# Peripherals.net
KiCad netlist of a schematic drawn in Altium Designer
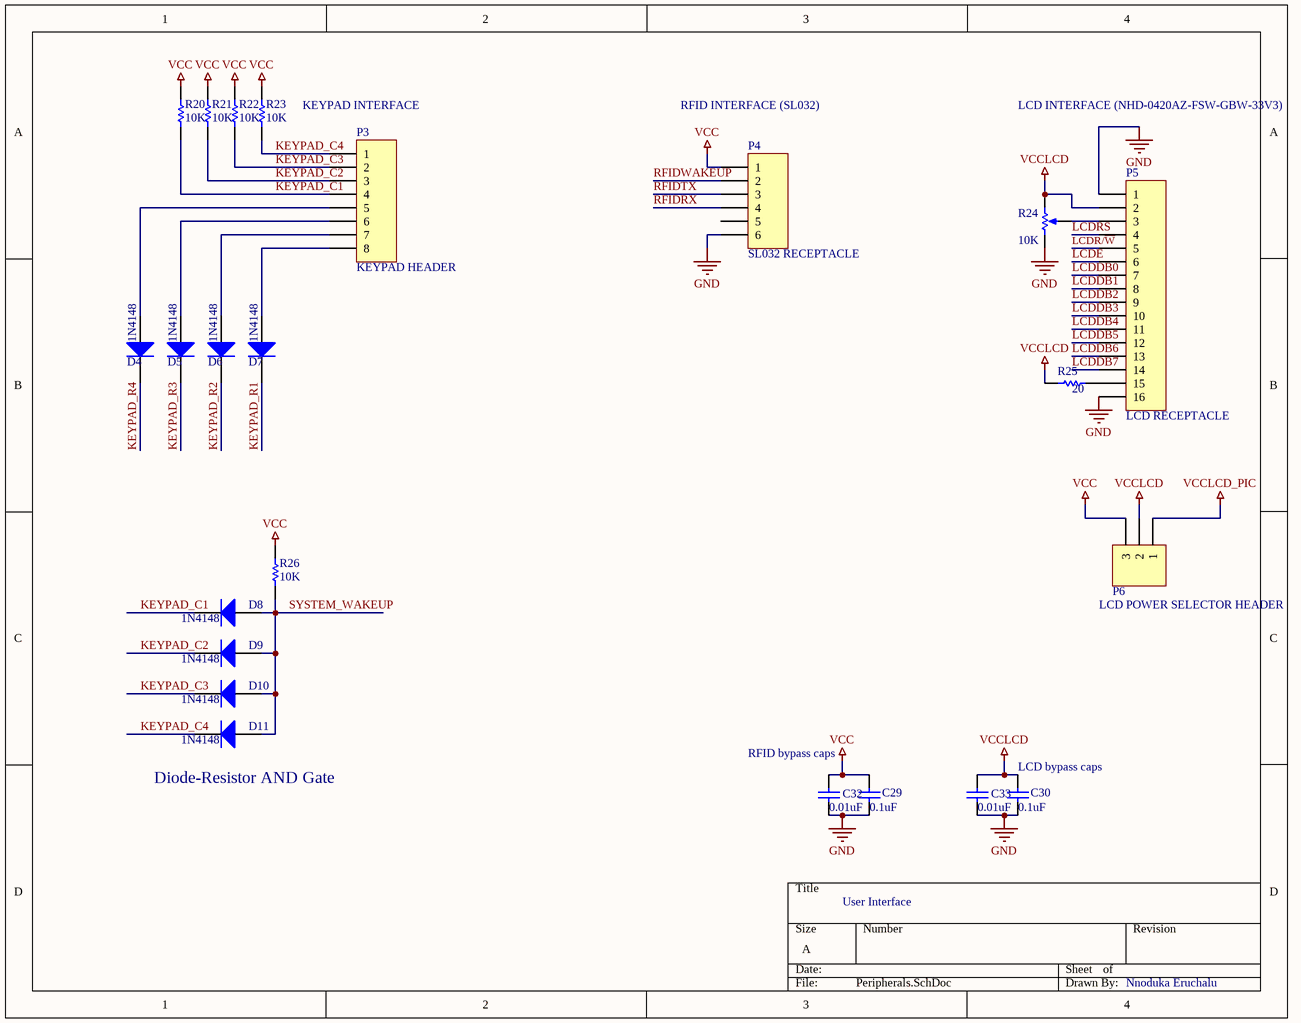
[diagram p0: Peripherals.SchDoc]

(export (version "E")
  (design (tool "Eeschema 10.0.6"))
  (components
    (comp (ref "C29")
      (value "0.1uF")
      (footprint "2012[0805]")
      (description "Ceramic Chip Capacitor - Standard")
      (fields (field (name "Comment") "C2012X7R1H104K/0.85") (field (name "PUBLISHER") "Altium Limited"))
      (libsource (lib "KEMET Chip Capacitor") (part "C0805"))
    )
    (comp (ref "C30")
      (value "0.1uF")
      (footprint "2012[0805]")
      (description "Ceramic Chip Capacitor - Standard")
      (fields (field (name "Comment") "C2012X7R1H104K/0.85") (field (name "PUBLISHER") "Altium Limited"))
      (libsource (lib "KEMET Chip Capacitor") (part "C0805"))
    )
    (comp (ref "C32")
      (value "0.01uF")
      (footprint "2012[0805]")
      (description "Ceramic Chip Capacitor - Standard")
      (fields (field (name "Comment") "C2012X7R2E103K") (field (name "PUBLISHER") "Altium Limited"))
      (libsource (lib "KEMET Chip Capacitor") (part "C0805"))
    )
    (comp (ref "C33")
      (value "0.01uF")
      (footprint "2012[0805]")
      (description "Ceramic Chip Capacitor - Standard")
      (fields (field (name "Comment") "C2012X7R2E103K") (field (name "PUBLISHER") "Altium Limited"))
      (libsource (lib "KEMET Chip Capacitor") (part "C0805"))
    )
    (comp (ref "D4")
      (value "1N4148")
      (footprint "easypay:SOD123")
      (description "High Conductance Fast Diode")
      (fields (field (name "PUBLISHER") "Altium Limited"))
      (libsource (lib "Miscellaneous Devices") (part "Diode 1N4148"))
    )
    (comp (ref "D5")
      (value "1N4148")
      (footprint "easypay:SOD123")
      (description "High Conductance Fast Diode")
      (fields (field (name "PUBLISHER") "Altium Limited"))
      (libsource (lib "Miscellaneous Devices") (part "Diode 1N4148"))
    )
    (comp (ref "D6")
      (value "1N4148")
      (footprint "easypay:SOD123")
      (description "High Conductance Fast Diode")
      (fields (field (name "PUBLISHER") "Altium Limited"))
      (libsource (lib "Miscellaneous Devices") (part "Diode 1N4148"))
    )
    (comp (ref "D7")
      (value "1N4148")
      (footprint "easypay:SOD123")
      (description "High Conductance Fast Diode")
      (fields (field (name "PUBLISHER") "Altium Limited"))
      (libsource (lib "Miscellaneous Devices") (part "Diode 1N4148"))
    )
    (comp (ref "D8")
      (value "1N4148")
      (footprint "easypay:SOD123")
      (description "High Conductance Fast Diode")
      (fields (field (name "PUBLISHER") "Altium Limited"))
      (libsource (lib "Miscellaneous Devices") (part "Diode 1N4148"))
    )
    (comp (ref "D9")
      (value "1N4148")
      (footprint "easypay:SOD123")
      (description "High Conductance Fast Diode")
      (fields (field (name "PUBLISHER") "Altium Limited"))
      (libsource (lib "Miscellaneous Devices") (part "Diode 1N4148"))
    )
    (comp (ref "D10")
      (value "1N4148")
      (footprint "easypay:SOD123")
      (description "High Conductance Fast Diode")
      (fields (field (name "PUBLISHER") "Altium Limited"))
      (libsource (lib "Miscellaneous Devices") (part "Diode 1N4148"))
    )
    (comp (ref "D11")
      (value "1N4148")
      (footprint "easypay:SOD123")
      (description "High Conductance Fast Diode")
      (fields (field (name "PUBLISHER") "Altium Limited"))
      (libsource (lib "Miscellaneous Devices") (part "Diode 1N4148"))
    )
    (comp (ref "P3")
      (value "KEYPAD HEADER")
      (footprint "HDR1X8")
      (description "Header, 8-Pin")
      (fields (field (name "PUBLISHER") "Altium Limited"))
      (libsource (lib "Miscellaneous Connectors") (part "Header 8"))
    )
    (comp (ref "P4")
      (value "SL032 RECEPTACLE")
      (footprint "HDR1X6")
      (description "Header, 6-Pin")
      (fields (field (name "PUBLISHER") "Altium Limited"))
      (libsource (lib "Miscellaneous Connectors") (part "Header 6"))
    )
    (comp (ref "P5")
      (value "LCD RECEPTACLE")
      (footprint "HDR1X16")
      (description "Header, 16-Pin")
      (fields (field (name "PUBLISHER") "Altium Limited"))
      (libsource (lib "Miscellaneous Connectors") (part "Header 16"))
    )
    (comp (ref "P6")
      (value "LCD POWER SELECTOR HEADER")
      (footprint "HDR1X3")
      (description "Header, 3-Pin")
      (fields (field (name "PUBLISHER") "Altium Limited"))
      (libsource (lib "Miscellaneous Connectors") (part "Header 3"))
    )
    (comp (ref "R20")
      (value "10K")
      (footprint "Miscellaneous Devices:2012[0805]")
      (description "Resistor")
      (fields (field (name "Comment") "ERJ-6GEYJ103V") (field (name "PUBLISHER") "Altium Limited"))
      (libsource (lib "Miscellaneous Devices") (part "Res1"))
    )
    (comp (ref "R21")
      (value "10K")
      (footprint "Miscellaneous Devices:2012[0805]")
      (description "Resistor")
      (fields (field (name "Comment") "ERJ-6GEYJ103V") (field (name "PUBLISHER") "Altium Limited"))
      (libsource (lib "Miscellaneous Devices") (part "Res1"))
    )
    (comp (ref "R22")
      (value "10K")
      (footprint "Miscellaneous Devices:2012[0805]")
      (description "Resistor")
      (fields (field (name "Comment") "ERJ-6GEYJ103V") (field (name "PUBLISHER") "Altium Limited"))
      (libsource (lib "Miscellaneous Devices") (part "Res1"))
    )
    (comp (ref "R23")
      (value "10K")
      (footprint "Miscellaneous Devices:2012[0805]")
      (description "Resistor")
      (fields (field (name "Comment") "ERJ-6GEYJ103V") (field (name "PUBLISHER") "Altium Limited"))
      (libsource (lib "Miscellaneous Devices") (part "Res1"))
    )
    (comp (ref "R24")
      (value "10K")
      (footprint "TC33")
      (description "Potentiometer")
      (fields (field (name "Comment") "TC33X-2-103E") (field (name "PUBLISHER") "Altium Limited"))
      (libsource (lib "Miscellaneous Devices") (part "RPot"))
    )
    (comp (ref "R25")
      (value "20")
      (footprint "Miscellaneous Devices:2012[0805]")
      (description "Resistor")
      (fields (field (name "Comment") "ERJ-6GEYJ200V") (field (name "PUBLISHER") "Altium Limited"))
      (libsource (lib "Miscellaneous Devices") (part "Res1"))
    )
    (comp (ref "R26")
      (value "10K")
      (footprint "Miscellaneous Devices:2012[0805]")
      (description "Resistor")
      (fields (field (name "Comment") "ERJ-6GEYJ103V") (field (name "PUBLISHER") "Altium Limited"))
      (libsource (lib "Miscellaneous Devices") (part "Res1"))
    )
  )
  (nets
    (net (code "1") (name "/KEYPAD_C1") (class "Default")
      (node (ref "D8") (pin "2") (pinfunction "K_2") (pintype "passive"))
      (node (ref "P3") (pin "4") (pinfunction "4_4") (pintype "passive"))
      (node (ref "R20") (pin "2") (pinfunction "2_2") (pintype "passive"))
    )
    (net (code "2") (name "/KEYPAD_C2") (class "Default")
      (node (ref "D9") (pin "2") (pinfunction "K_2") (pintype "passive"))
      (node (ref "P3") (pin "3") (pinfunction "3_3") (pintype "passive"))
      (node (ref "R21") (pin "2") (pinfunction "2_2") (pintype "passive"))
    )
    (net (code "3") (name "/KEYPAD_C3") (class "Default")
      (node (ref "D10") (pin "2") (pinfunction "K_2") (pintype "passive"))
      (node (ref "P3") (pin "2") (pinfunction "2_2") (pintype "passive"))
      (node (ref "R22") (pin "2") (pinfunction "2_2") (pintype "passive"))
    )
    (net (code "4") (name "/KEYPAD_C4") (class "Default")
      (node (ref "D11") (pin "2") (pinfunction "K_2") (pintype "passive"))
      (node (ref "P3") (pin "1") (pinfunction "1_1") (pintype "passive"))
      (node (ref "R23") (pin "2") (pinfunction "2_2") (pintype "passive"))
    )
    (net (code "5") (name "/KEYPAD_R1") (class "Default")
      (node (ref "D7") (pin "2") (pinfunction "K_2") (pintype "passive"))
    )
    (net (code "6") (name "/KEYPAD_R2") (class "Default")
      (node (ref "D6") (pin "2") (pinfunction "K_2") (pintype "passive"))
    )
    (net (code "7") (name "/KEYPAD_R3") (class "Default")
      (node (ref "D5") (pin "2") (pinfunction "K_2") (pintype "passive"))
    )
    (net (code "8") (name "/KEYPAD_R4") (class "Default")
      (node (ref "D4") (pin "2") (pinfunction "K_2") (pintype "passive"))
    )
    (net (code "9") (name "/LCDDB0") (class "Default")
      (node (ref "P5") (pin "7") (pinfunction "7_7") (pintype "passive"))
    )
    (net (code "10") (name "/LCDDB1") (class "Default")
      (node (ref "P5") (pin "8") (pinfunction "8_8") (pintype "passive"))
    )
    (net (code "11") (name "/LCDDB2") (class "Default")
      (node (ref "P5") (pin "9") (pinfunction "9_9") (pintype "passive"))
    )
    (net (code "12") (name "/LCDDB3") (class "Default")
      (node (ref "P5") (pin "10") (pinfunction "10_10") (pintype "passive"))
    )
    (net (code "13") (name "/LCDDB4") (class "Default")
      (node (ref "P5") (pin "11") (pinfunction "11_11") (pintype "passive"))
    )
    (net (code "14") (name "/LCDDB5") (class "Default")
      (node (ref "P5") (pin "12") (pinfunction "12_12") (pintype "passive"))
    )
    (net (code "15") (name "/LCDDB6") (class "Default")
      (node (ref "P5") (pin "13") (pinfunction "13_13") (pintype "passive"))
    )
    (net (code "16") (name "/LCDDB7") (class "Default")
      (node (ref "P5") (pin "14") (pinfunction "14_14") (pintype "passive"))
    )
    (net (code "17") (name "/LCDE") (class "Default")
      (node (ref "P5") (pin "6") (pinfunction "6_6") (pintype "passive"))
    )
    (net (code "18") (name "/LCDRS") (class "Default")
      (node (ref "P5") (pin "4") (pinfunction "4_4") (pintype "passive"))
    )
    (net (code "19") (name "/LCDR{slash}~{W}") (class "Default")
      (node (ref "P5") (pin "5") (pinfunction "5_5") (pintype "passive"))
    )
    (net (code "20") (name "/RFIDRX") (class "Default")
      (node (ref "P4") (pin "4") (pinfunction "4_4") (pintype "passive"))
    )
    (net (code "21") (name "/RFIDTX") (class "Default")
      (node (ref "P4") (pin "3") (pinfunction "3_3") (pintype "passive"))
    )
    (net (code "22") (name "/RFIDWAKEUP") (class "Default")
      (node (ref "P4") (pin "2") (pinfunction "2_2") (pintype "passive"))
    )
    (net (code "23") (name "/SYSTEM_WAKEUP") (class "Default")
      (node (ref "D10") (pin "1") (pinfunction "A_1") (pintype "passive"))
      (node (ref "D11") (pin "1") (pinfunction "A_1") (pintype "passive"))
      (node (ref "D8") (pin "1") (pinfunction "A_1") (pintype "passive"))
      (node (ref "D9") (pin "1") (pinfunction "A_1") (pintype "passive"))
      (node (ref "R26") (pin "2") (pinfunction "2_2") (pintype "passive"))
    )
    (net (code "24") (name "GND") (class "Default")
      (node (ref "C29") (pin "1") (pinfunction "1_1") (pintype "passive"))
      (node (ref "C30") (pin "1") (pinfunction "1_1") (pintype "passive"))
      (node (ref "C32") (pin "1") (pinfunction "1_1") (pintype "passive"))
      (node (ref "C33") (pin "1") (pinfunction "1_1") (pintype "passive"))
      (node (ref "P4") (pin "6") (pinfunction "6_6") (pintype "passive"))
      (node (ref "P5") (pin "1") (pinfunction "1_1") (pintype "passive"))
      (node (ref "P5") (pin "16") (pinfunction "16_16") (pintype "passive"))
      (node (ref "R24") (pin "1") (pinfunction "TOP_1") (pintype "passive"))
    )
    (net (code "25") (name "Net-(D4-A)") (class "Default")
      (node (ref "D4") (pin "1") (pinfunction "A_1") (pintype "passive"))
      (node (ref "P3") (pin "5") (pinfunction "5_5") (pintype "passive"))
    )
    (net (code "26") (name "Net-(D5-A)") (class "Default")
      (node (ref "D5") (pin "1") (pinfunction "A_1") (pintype "passive"))
      (node (ref "P3") (pin "6") (pinfunction "6_6") (pintype "passive"))
    )
    (net (code "27") (name "Net-(D6-A)") (class "Default")
      (node (ref "D6") (pin "1") (pinfunction "A_1") (pintype "passive"))
      (node (ref "P3") (pin "7") (pinfunction "7_7") (pintype "passive"))
    )
    (net (code "28") (name "Net-(D7-A)") (class "Default")
      (node (ref "D7") (pin "1") (pinfunction "A_1") (pintype "passive"))
      (node (ref "P3") (pin "8") (pinfunction "8_8") (pintype "passive"))
    )
    (net (code "29") (name "Net-(P5-Pad15)") (class "Default")
      (node (ref "P5") (pin "15") (pinfunction "15_15") (pintype "passive"))
      (node (ref "R25") (pin "2") (pinfunction "2_2") (pintype "passive"))
    )
    (net (code "30") (name "Net-(R24-TAP)") (class "Default")
      (node (ref "P5") (pin "3") (pinfunction "3_3") (pintype "passive"))
      (node (ref "R24") (pin "3") (pinfunction "TAP_3") (pintype "passive"))
    )
    (net (code "31") (name "VCC") (class "Default")
      (node (ref "C29") (pin "2") (pinfunction "2_2") (pintype "passive"))
      (node (ref "C32") (pin "2") (pinfunction "2_2") (pintype "passive"))
      (node (ref "P4") (pin "1") (pinfunction "1_1") (pintype "passive"))
      (node (ref "P6") (pin "3") (pinfunction "3_3") (pintype "passive"))
      (node (ref "R20") (pin "1") (pinfunction "1_1") (pintype "passive"))
      (node (ref "R21") (pin "1") (pinfunction "1_1") (pintype "passive"))
      (node (ref "R22") (pin "1") (pinfunction "1_1") (pintype "passive"))
      (node (ref "R23") (pin "1") (pinfunction "1_1") (pintype "passive"))
      (node (ref "R26") (pin "1") (pinfunction "1_1") (pintype "passive"))
    )
    (net (code "32") (name "VCCLCD") (class "Default")
      (node (ref "C30") (pin "2") (pinfunction "2_2") (pintype "passive"))
      (node (ref "C33") (pin "2") (pinfunction "2_2") (pintype "passive"))
      (node (ref "P5") (pin "2") (pinfunction "2_2") (pintype "passive"))
      (node (ref "P6") (pin "2") (pinfunction "2_2") (pintype "passive"))
      (node (ref "R24") (pin "2") (pinfunction "BOT_2") (pintype "passive"))
      (node (ref "R25") (pin "1") (pinfunction "1_1") (pintype "passive"))
    )
    (net (code "33") (name "VCCLCD_PIC") (class "Default")
      (node (ref "P6") (pin "1") (pinfunction "1_1") (pintype "passive"))
    )
    (net (code "34") (name "unconnected-(P4-Pad5)") (class "Default")
      (node (ref "P4") (pin "5") (pinfunction "5_5") (pintype "passive"))
    )
  )
)
